# SCH_Aether_Zero_R0_3.net
KiCad netlist of a schematic drawn in EasyEDA
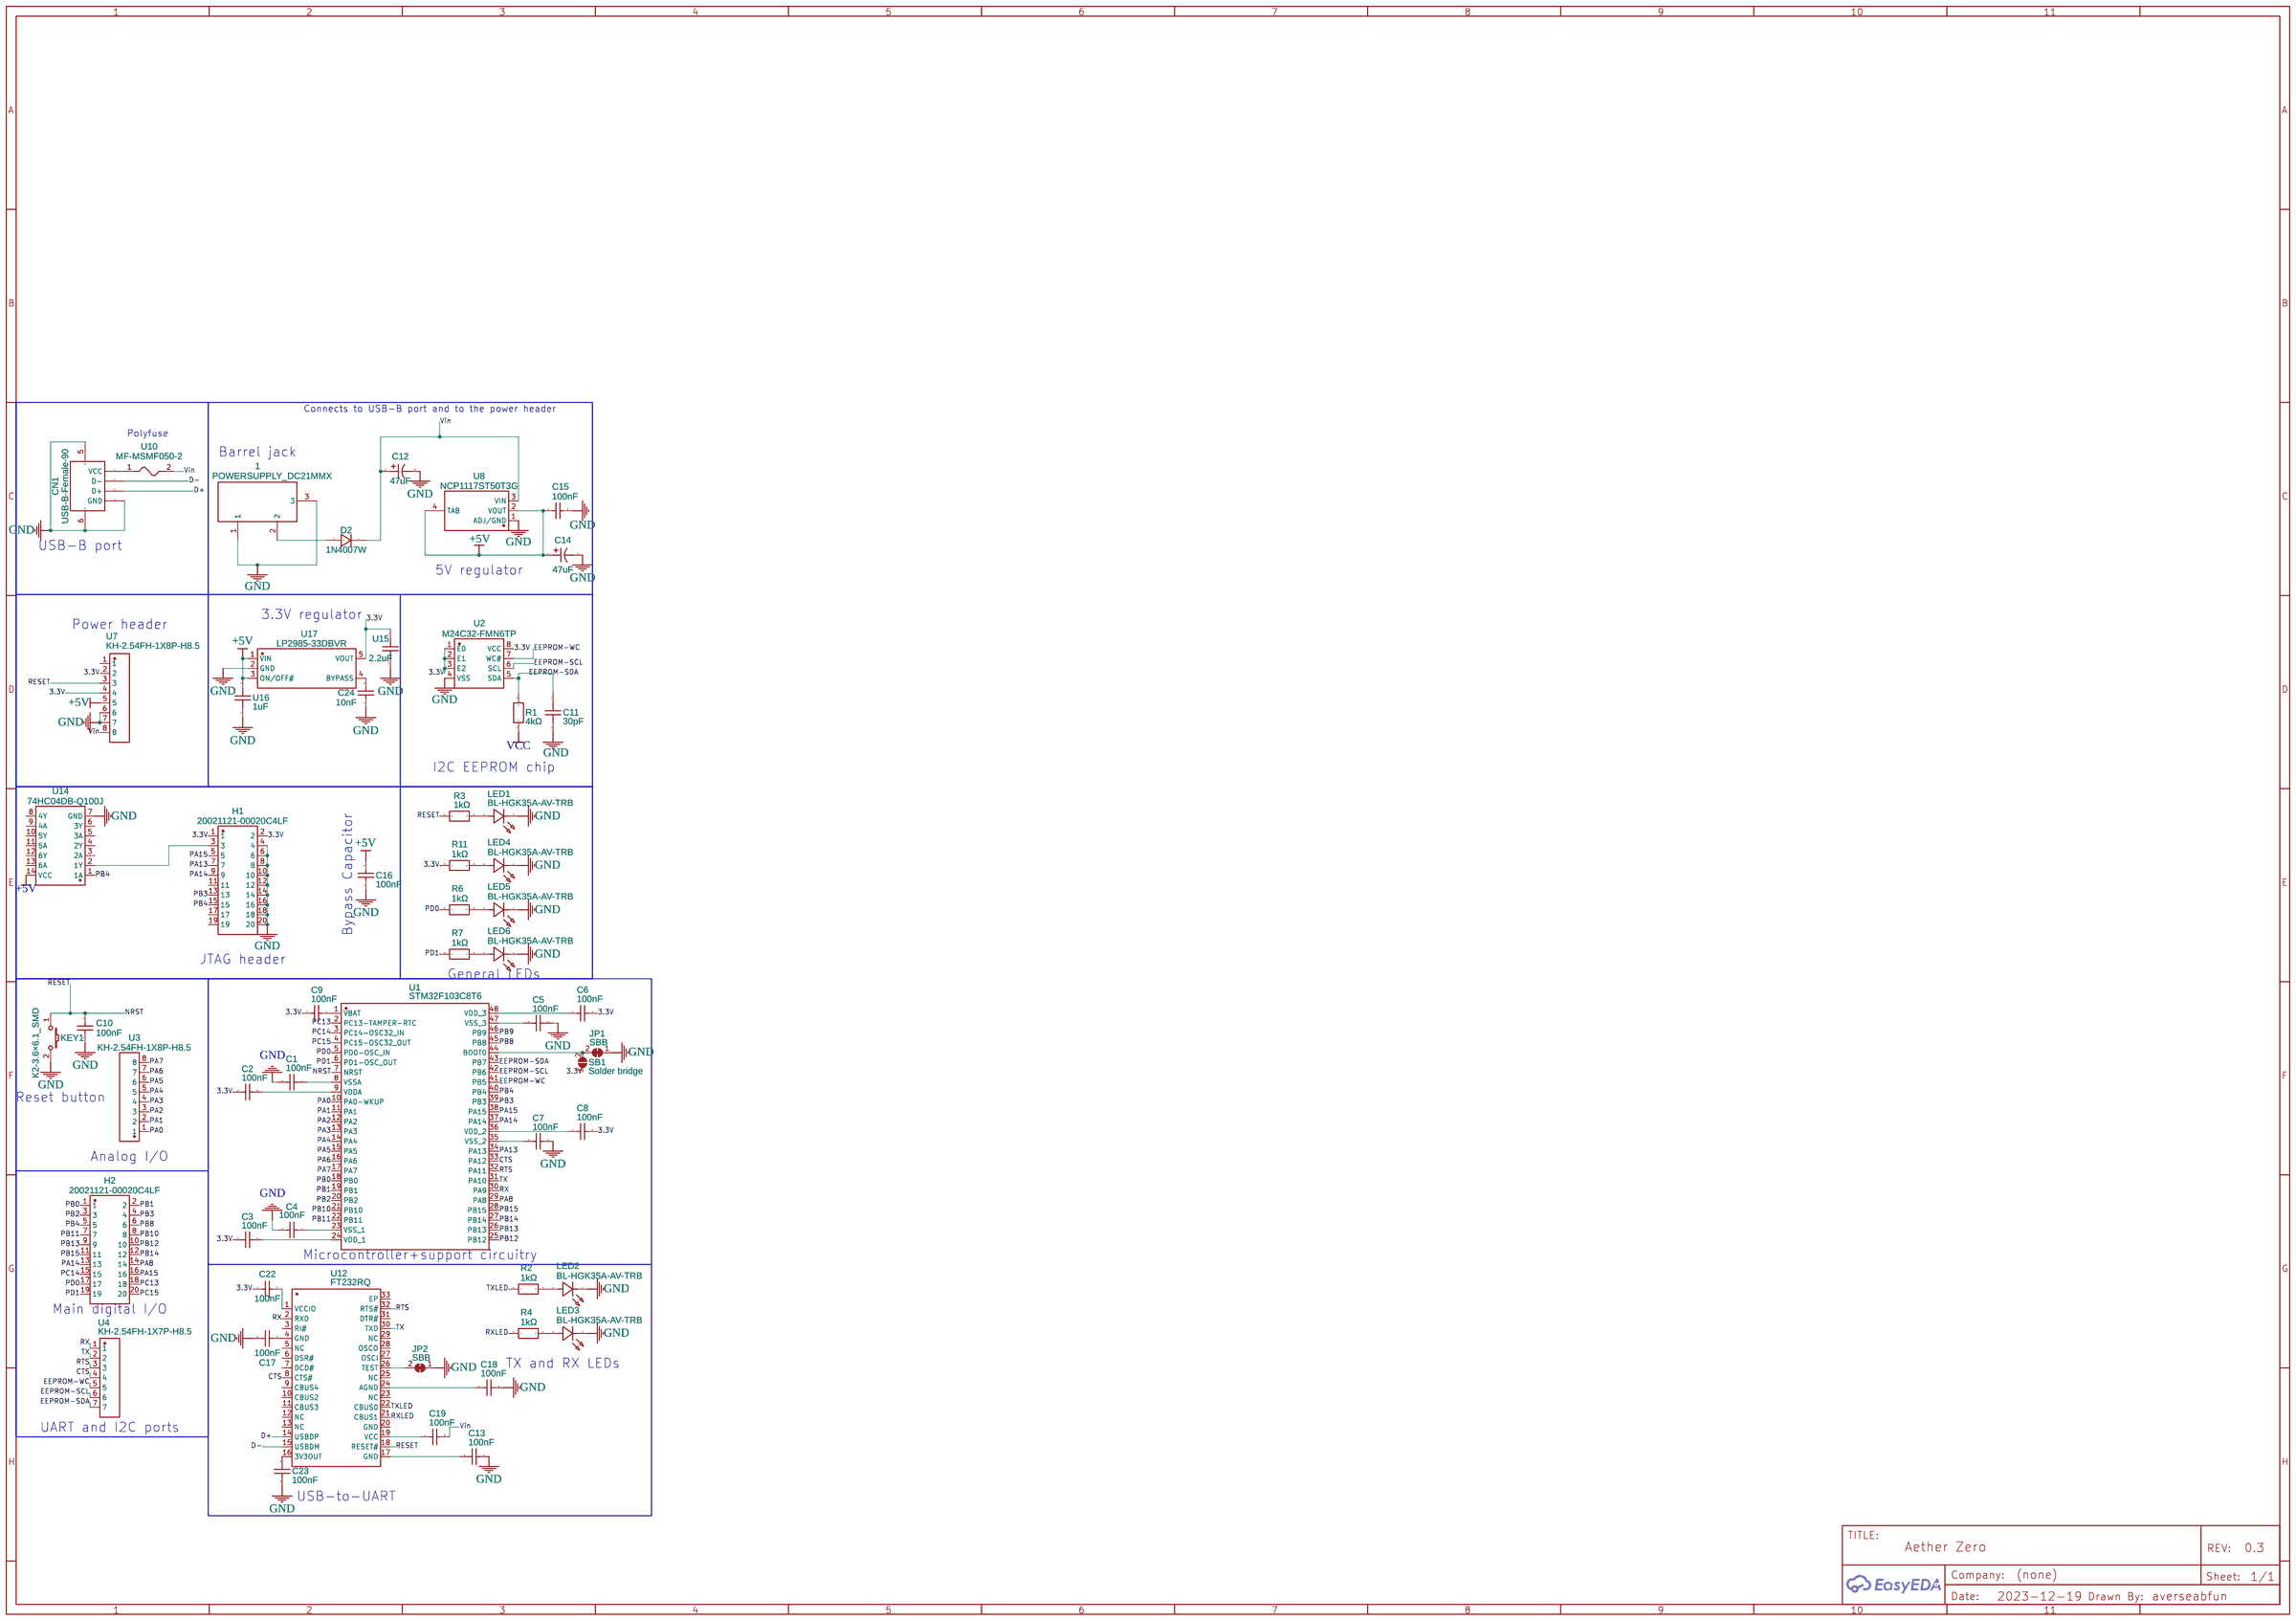
[diagram p0: schematic sheet]

(export (version "E")
  (design (tool "Eeschema 10.0.6"))
  (components
    (comp (ref "1") (value "POWERSUPPLY_DC21MMX") (libsource (lib "") (part "POWERSUPPLY_DC21MMX")))
    (comp (ref "C1")
      (value "100nF")
      (fields (field (name "Manufacturer Part") "0402B104K160NT") (field (name "Manufacturer") "FH(风华)"))
      (libsource (lib "") (part "0402B104K160NT_2"))
    )
    (comp (ref "C2")
      (value "100nF")
      (fields (field (name "Manufacturer Part") "0402B104K160NT") (field (name "Manufacturer") "FH(风华)"))
      (libsource (lib "") (part "0402B104K160NT_2"))
    )
    (comp (ref "C3")
      (value "100nF")
      (fields (field (name "Manufacturer Part") "0402B104K160NT") (field (name "Manufacturer") "FH(风华)"))
      (libsource (lib "") (part "0402B104K160NT_2"))
    )
    (comp (ref "C4")
      (value "100nF")
      (fields (field (name "Manufacturer Part") "0402B104K160NT") (field (name "Manufacturer") "FH(风华)"))
      (libsource (lib "") (part "0402B104K160NT_2"))
    )
    (comp (ref "C5")
      (value "100nF")
      (fields (field (name "Manufacturer Part") "0402B104K160NT") (field (name "Manufacturer") "FH(风华)"))
      (libsource (lib "") (part "0402B104K160NT_1"))
    )
    (comp (ref "C6")
      (value "100nF")
      (fields (field (name "Manufacturer Part") "0402B104K160NT") (field (name "Manufacturer") "FH(风华)"))
      (libsource (lib "") (part "0402B104K160NT_1"))
    )
    (comp (ref "C7")
      (value "100nF")
      (fields (field (name "Manufacturer Part") "0402B104K160NT") (field (name "Manufacturer") "FH(风华)"))
      (libsource (lib "") (part "0402B104K160NT_1"))
    )
    (comp (ref "C8")
      (value "100nF")
      (fields (field (name "Manufacturer Part") "0402B104K160NT") (field (name "Manufacturer") "FH(风华)"))
      (libsource (lib "") (part "0402B104K160NT_1"))
    )
    (comp (ref "C9")
      (value "100nF")
      (fields (field (name "Manufacturer Part") "0402B104K160NT") (field (name "Manufacturer") "FH(风华)"))
      (libsource (lib "") (part "0402B104K160NT_2"))
    )
    (comp (ref "C10")
      (value "100nF")
      (fields (field (name "Manufacturer Part") "0402B104K160NT") (field (name "Manufacturer") "FH(风华)"))
      (libsource (lib "") (part "0402B104K160NT"))
    )
    (comp (ref "C11")
      (value "30pF")
      (fields
        (field (name "Manufacturer Part") "AC0402JRNPO9BN300")
        (field (name "Manufacturer") "YAGEO(国巨)")
      )
      (libsource (lib "") (part "AC0402JRNPO9BN300"))
    )
    (comp (ref "C12")
      (value "47uF")
      (fields
        (field (name "Manufacturer Part") "RVT47UF35V67RV0039")
        (field (name "Manufacturer") "KNSCHA(科尼盛)")
      )
      (libsource (lib "") (part "RVT47UF35V67RV0039"))
    )
    (comp (ref "C13")
      (value "100nF")
      (fields (field (name "Manufacturer Part") "0402B104K160NT") (field (name "Manufacturer") "FH(风华)"))
      (libsource (lib "") (part "0402B104K160NT_1"))
    )
    (comp (ref "C14")
      (value "47uF")
      (fields
        (field (name "Manufacturer Part") "RVT47UF35V67RV0039")
        (field (name "Manufacturer") "KNSCHA(科尼盛)")
      )
      (libsource (lib "") (part "RVT47UF35V67RV0039"))
    )
    (comp (ref "C15")
      (value "100nF")
      (fields (field (name "Manufacturer Part") "0402B104K160NT") (field (name "Manufacturer") "FH(风华)"))
      (libsource (lib "") (part "0402B104K160NT_1"))
    )
    (comp (ref "C16")
      (value "100nF")
      (fields (field (name "Manufacturer Part") "0402B104K160NT") (field (name "Manufacturer") "FH(风华)"))
      (libsource (lib "") (part "0402B104K160NT_3"))
    )
    (comp (ref "C17")
      (value "100nF")
      (fields (field (name "Manufacturer Part") "0402B104K160NT") (field (name "Manufacturer") "FH(风华)"))
      (libsource (lib "") (part "0402B104K160NT_2"))
    )
    (comp (ref "C18")
      (value "100nF")
      (fields (field (name "Manufacturer Part") "0402B104K160NT") (field (name "Manufacturer") "FH(风华)"))
      (libsource (lib "") (part "0402B104K160NT_1"))
    )
    (comp (ref "C19")
      (value "100nF")
      (fields (field (name "Manufacturer Part") "0402B104K160NT") (field (name "Manufacturer") "FH(风华)"))
      (libsource (lib "") (part "0402B104K160NT_1"))
    )
    (comp (ref "C22")
      (value "100nF")
      (fields (field (name "Manufacturer Part") "0402B104K160NT") (field (name "Manufacturer") "FH(风华)"))
      (libsource (lib "") (part "0402B104K160NT_2"))
    )
    (comp (ref "C23")
      (value "100nF")
      (fields (field (name "Manufacturer Part") "0402B104K160NT") (field (name "Manufacturer") "FH(风华)"))
      (libsource (lib "") (part "0402B104K160NT"))
    )
    (comp (ref "C24")
      (value "10nF")
      (fields (field (name "Manufacturer Part") "0402B103K500NT") (field (name "Manufacturer") "FH(风华)"))
      (libsource (lib "") (part "0402B103K500NT"))
    )
    (comp (ref "CN1")
      (value "USB-B-Female-90")
      (fields (field (name "Manufacturer Part") "921-111A1010D10200") (field (name "Manufacturer") "精拓金"))
      (libsource (lib "") (part "USB-B-Female-90"))
    )
    (comp (ref "D2")
      (value "1N4007W")
      (fields (field (name "Manufacturer") "BLUE ROCKET"))
      (libsource (lib "") (part "1N4007W"))
    )
    (comp (ref "H1")
      (value "20021121-00020C4LF")
      (fields (field (name "Manufacturer") "Amphenol"))
      (libsource (lib "") (part "20021121-00020C4LF"))
    )
    (comp (ref "H2")
      (value "20021121-00020C4LF")
      (fields (field (name "Manufacturer") "Amphenol"))
      (libsource (lib "") (part "20021121-00020C4LF"))
    )
    (comp (ref "JP1") (value "SBB") (libsource (lib "") (part "SBB")))
    (comp (ref "JP2") (value "SBB") (libsource (lib "") (part "SBB")))
    (comp (ref "KEY1")
      (value "K2-3.6×6.1_SMD")
      (fields (field (name "Manufacturer Part") "K2-1107ST-A4SW-06"))
      (libsource (lib "") (part "K2-3.6×6.1_SMD"))
    )
    (comp (ref "LED1")
      (value "BL-HGK35A-AV-TRB")
      (fields (field (name "Manufacturer") "BrtLed(佰鸿)"))
      (libsource (lib "") (part "BL-HGK35A-AV-TRB"))
    )
    (comp (ref "LED2")
      (value "BL-HGK35A-AV-TRB")
      (fields (field (name "Manufacturer") "BrtLed(佰鸿)"))
      (libsource (lib "") (part "BL-HGK35A-AV-TRB"))
    )
    (comp (ref "LED3")
      (value "BL-HGK35A-AV-TRB")
      (fields (field (name "Manufacturer") "BrtLed(佰鸿)"))
      (libsource (lib "") (part "BL-HGK35A-AV-TRB"))
    )
    (comp (ref "LED4")
      (value "BL-HGK35A-AV-TRB")
      (fields (field (name "Manufacturer") "BrtLed(佰鸿)"))
      (libsource (lib "") (part "BL-HGK35A-AV-TRB"))
    )
    (comp (ref "LED5")
      (value "BL-HGK35A-AV-TRB")
      (fields (field (name "Manufacturer") "BrtLed(佰鸿)"))
      (libsource (lib "") (part "BL-HGK35A-AV-TRB"))
    )
    (comp (ref "LED6")
      (value "BL-HGK35A-AV-TRB")
      (fields (field (name "Manufacturer") "BrtLed(佰鸿)"))
      (libsource (lib "") (part "BL-HGK35A-AV-TRB"))
    )
    (comp (ref "R1")
      (value "4kΩ")
      (fields (field (name "Manufacturer Part") "RN732BTTD4001B25") (field (name "Manufacturer") "KOA"))
      (libsource (lib "") (part "RN732BTTD4001B25"))
    )
    (comp (ref "R2")
      (value "1kΩ")
      (fields (field (name "Manufacturer Part") "CR-03JA7----1K") (field (name "Manufacturer") "Viking Tech"))
      (libsource (lib "") (part "CR-03JA7----1K"))
    )
    (comp (ref "R3")
      (value "1kΩ")
      (fields (field (name "Manufacturer Part") "CR-03JA7----1K") (field (name "Manufacturer") "Viking Tech"))
      (libsource (lib "") (part "CR-03JA7----1K_1"))
    )
    (comp (ref "R4")
      (value "1kΩ")
      (fields (field (name "Manufacturer Part") "CR-03JA7----1K") (field (name "Manufacturer") "Viking Tech"))
      (libsource (lib "") (part "CR-03JA7----1K"))
    )
    (comp (ref "R6")
      (value "1kΩ")
      (fields (field (name "Manufacturer Part") "CR-03JA7----1K") (field (name "Manufacturer") "Viking Tech"))
      (libsource (lib "") (part "CR-03JA7----1K"))
    )
    (comp (ref "R7")
      (value "1kΩ")
      (fields (field (name "Manufacturer Part") "CR-03JA7----1K") (field (name "Manufacturer") "Viking Tech"))
      (libsource (lib "") (part "CR-03JA7----1K"))
    )
    (comp (ref "R11")
      (value "1kΩ")
      (fields (field (name "Manufacturer Part") "CR-03JA7----1K") (field (name "Manufacturer") "Viking Tech"))
      (libsource (lib "") (part "CR-03JA7----1K"))
    )
    (comp (ref "SB1")
      (value "Solder bridge")
      (fields (field (name "Manufacturer Part") "DNP"))
      (libsource (lib "") (part "Solder bridge"))
    )
    (comp (ref "U1")
      (value "STM32F103C8T6")
      (fields (field (name "Manufacturer") "ST(意法半导体)"))
      (libsource (lib "") (part "STM32F103C8T6"))
    )
    (comp (ref "U2")
      (value "M24C32-FMN6TP")
      (fields (field (name "Manufacturer") "ST(意法半导体)"))
      (libsource (lib "") (part "M24C32-FMN6TP"))
    )
    (comp (ref "U3")
      (value "KH-2.54FH-1X8P-H8.5")
      (fields (field (name "Manufacturer") "kinghelm(金航标)"))
      (libsource (lib "") (part "KH-2.54FH-1X8P-H8.5_1"))
    )
    (comp (ref "U4")
      (value "KH-2.54FH-1X7P-H8.5")
      (fields (field (name "Manufacturer") "kinghelm(金航标)"))
      (libsource (lib "") (part "KH-2.54FH-1X7P-H8.5"))
    )
    (comp (ref "U7")
      (value "KH-2.54FH-1X8P-H8.5")
      (fields (field (name "Manufacturer") "kinghelm(金航标)"))
      (libsource (lib "") (part "KH-2.54FH-1X8P-H8.5"))
    )
    (comp (ref "U8")
      (value "NCP1117ST50T3G")
      (fields (field (name "Manufacturer") "onsemi(安森美)"))
      (libsource (lib "") (part "NCP1117ST50T3G"))
    )
    (comp (ref "U10")
      (value "MF-MSMF050-2")
      (fields (field (name "Manufacturer") "BOURNS"))
      (libsource (lib "") (part "MF-MSMF050-2"))
    )
    (comp (ref "U12")
      (value "FT232RQ")
      (fields (field (name "Manufacturer Part") "FT232RQ-REEL") (field (name "Manufacturer") "FTDI(飞特帝亚)"))
      (libsource (lib "") (part "FT232RQ"))
    )
    (comp (ref "U14")
      (value "74HC04DB-Q100J")
      (fields (field (name "Manufacturer") "Nexperia(安世)"))
      (libsource (lib "") (part "74HC04DB-Q100J"))
    )
    (comp (ref "U15")
      (value "2.2uF")
      (fields (field (name "Manufacturer Part") "0805X225K250CT") (field (name "Manufacturer") "Walsin(华新科)"))
      (libsource (lib "") (part "0805X225K250CT_C5122273"))
    )
    (comp (ref "U16")
      (value "1uF")
      (fields (field (name "Manufacturer Part") "CGA5L3X8R1H105KT0Y0N") (field (name "Manufacturer") "TDK"))
      (libsource (lib "") (part "CGA5L3X8R1H105KT0Y0N"))
    )
    (comp (ref "U17")
      (value "LP2985-33DBVR")
      (fields (field (name "Manufacturer") "TI(德州仪器)"))
      (libsource (lib "") (part "LP2985-33DBVR"))
    )
  )
  (nets
    (net (code "1") (name "+5V") (class "Default")
      (node (ref "C14") (pin "1") (pinfunction "1_1") (pintype "input"))
      (node (ref "C15") (pin "1") (pinfunction "1_1") (pintype "input"))
      (node (ref "C16") (pin "2") (pinfunction "2_2") (pintype "input"))
      (node (ref "U14") (pin "14") (pinfunction "VCC_14") (pintype "unspecified"))
      (node (ref "U16") (pin "2") (pinfunction "2_2") (pintype "unspecified"))
      (node (ref "U17") (pin "1") (pinfunction "VIN_1") (pintype "unspecified"))
      (node (ref "U17") (pin "3") (pinfunction "ON/OFF#_3") (pintype "unspecified"))
      (node (ref "U7") (pin "5") (pinfunction "5_5") (pintype "unspecified"))
      (node (ref "U8") (pin "2") (pinfunction "VOUT_2") (pintype "unspecified"))
      (node (ref "U8") (pin "4") (pinfunction "TAB_4") (pintype "unspecified"))
    )
    (net (code "2") (name "/3.3V") (class "Default")
      (node (ref "C2") (pin "2") (pinfunction "2_2") (pintype "input"))
      (node (ref "C22") (pin "2") (pinfunction "2_2") (pintype "input"))
      (node (ref "C3") (pin "2") (pinfunction "2_2") (pintype "input"))
      (node (ref "C6") (pin "2") (pinfunction "2_2") (pintype "input"))
      (node (ref "C8") (pin "2") (pinfunction "2_2") (pintype "input"))
      (node (ref "C9") (pin "2") (pinfunction "2_2") (pintype "input"))
      (node (ref "H1") (pin "1") (pinfunction "1_1") (pintype "unspecified"))
      (node (ref "H1") (pin "2") (pinfunction "2_2") (pintype "unspecified"))
      (node (ref "R11") (pin "1") (pinfunction "1_1") (pintype "unspecified"))
      (node (ref "SB1") (pin "1") (pinfunction "A_1") (pintype "unspecified"))
      (node (ref "U15") (pin "1") (pinfunction "1_1") (pintype "unspecified"))
      (node (ref "U17") (pin "5") (pinfunction "VOUT_5") (pintype "unspecified"))
      (node (ref "U2") (pin "1") (pinfunction "E0_1") (pintype "unspecified"))
      (node (ref "U2") (pin "2") (pinfunction "E1_2") (pintype "unspecified"))
      (node (ref "U2") (pin "3") (pinfunction "E2_3") (pintype "unspecified"))
      (node (ref "U2") (pin "8") (pinfunction "VCC_8") (pintype "unspecified"))
      (node (ref "U7") (pin "2") (pinfunction "2_2") (pintype "unspecified"))
      (node (ref "U7") (pin "4") (pinfunction "4_4") (pintype "unspecified"))
    )
    (net (code "3") (name "/CTS") (class "Default")
      (node (ref "U1") (pin "33") (pinfunction "PA12_33") (pintype "unspecified"))
      (node (ref "U12") (pin "8") (pinfunction "CTS#_8") (pintype "unspecified"))
      (node (ref "U4") (pin "4") (pinfunction "4_4") (pintype "unspecified"))
    )
    (net (code "4") (name "/D+") (class "Default")
      (node (ref "CN1") (pin "3") (pinfunction "D+_3") (pintype "input"))
      (node (ref "U12") (pin "14") (pinfunction "USBDP_14") (pintype "unspecified"))
    )
    (net (code "5") (name "/D-") (class "Default")
      (node (ref "CN1") (pin "2") (pinfunction "D-_2") (pintype "input"))
      (node (ref "U12") (pin "15") (pinfunction "USBDM_15") (pintype "unspecified"))
    )
    (net (code "6") (name "/EEPROM-SCL") (class "Default")
      (node (ref "U1") (pin "42") (pinfunction "PB6_42") (pintype "unspecified"))
      (node (ref "U2") (pin "6") (pinfunction "SCL_6") (pintype "unspecified"))
      (node (ref "U4") (pin "6") (pinfunction "6_6") (pintype "unspecified"))
    )
    (net (code "7") (name "/EEPROM-SDA") (class "Default")
      (node (ref "C11") (pin "1") (pinfunction "1_1") (pintype "unspecified"))
      (node (ref "R1") (pin "2") (pinfunction "2_2") (pintype "unspecified"))
      (node (ref "U1") (pin "43") (pinfunction "PB7_43") (pintype "unspecified"))
      (node (ref "U2") (pin "5") (pinfunction "SDA_5") (pintype "unspecified"))
      (node (ref "U4") (pin "7") (pinfunction "7_7") (pintype "unspecified"))
    )
    (net (code "8") (name "/EEPROM-WC") (class "Default")
      (node (ref "U1") (pin "41") (pinfunction "PB5_41") (pintype "unspecified"))
      (node (ref "U2") (pin "7") (pinfunction "WC#_7") (pintype "unspecified"))
      (node (ref "U4") (pin "5") (pinfunction "5_5") (pintype "unspecified"))
    )
    (net (code "9") (name "/NRST") (class "Default")
      (node (ref "C10") (pin "1") (pinfunction "1_1") (pintype "input"))
      (node (ref "KEY1") (pin "1") (pinfunction "1_1") (pintype "unspecified"))
      (node (ref "R3") (pin "2") (pinfunction "2_2") (pintype "unspecified"))
      (node (ref "U1") (pin "7") (pinfunction "NRST_7") (pintype "unspecified"))
      (node (ref "U12") (pin "18") (pinfunction "RESET#_18") (pintype "unspecified"))
      (node (ref "U7") (pin "3") (pinfunction "3_3") (pintype "unspecified"))
    )
    (net (code "10") (name "/PA0") (class "Default")
      (node (ref "U1") (pin "10") (pinfunction "PA0-WKUP_10") (pintype "unspecified"))
      (node (ref "U3") (pin "1") (pinfunction "1_1") (pintype "unspecified"))
    )
    (net (code "11") (name "/PA1") (class "Default")
      (node (ref "U1") (pin "11") (pinfunction "PA1_11") (pintype "unspecified"))
      (node (ref "U3") (pin "2") (pinfunction "2_2") (pintype "unspecified"))
    )
    (net (code "12") (name "/PA2") (class "Default")
      (node (ref "U1") (pin "12") (pinfunction "PA2_12") (pintype "unspecified"))
      (node (ref "U3") (pin "3") (pinfunction "3_3") (pintype "unspecified"))
    )
    (net (code "13") (name "/PA3") (class "Default")
      (node (ref "U1") (pin "13") (pinfunction "PA3_13") (pintype "unspecified"))
      (node (ref "U3") (pin "4") (pinfunction "4_4") (pintype "unspecified"))
    )
    (net (code "14") (name "/PA4") (class "Default")
      (node (ref "U1") (pin "14") (pinfunction "PA4_14") (pintype "unspecified"))
      (node (ref "U3") (pin "5") (pinfunction "5_5") (pintype "unspecified"))
    )
    (net (code "15") (name "/PA5") (class "Default")
      (node (ref "U1") (pin "15") (pinfunction "PA5_15") (pintype "unspecified"))
      (node (ref "U3") (pin "6") (pinfunction "6_6") (pintype "unspecified"))
    )
    (net (code "16") (name "/PA6") (class "Default")
      (node (ref "U1") (pin "16") (pinfunction "PA6_16") (pintype "unspecified"))
      (node (ref "U3") (pin "7") (pinfunction "7_7") (pintype "unspecified"))
    )
    (net (code "17") (name "/PA7") (class "Default")
      (node (ref "U1") (pin "17") (pinfunction "PA7_17") (pintype "unspecified"))
      (node (ref "U3") (pin "8") (pinfunction "8_8") (pintype "unspecified"))
    )
    (net (code "18") (name "/PA8") (class "Default")
      (node (ref "H2") (pin "14") (pinfunction "14_14") (pintype "unspecified"))
      (node (ref "U1") (pin "29") (pinfunction "PA8_29") (pintype "unspecified"))
    )
    (net (code "19") (name "/PA13") (class "Default")
      (node (ref "H1") (pin "7") (pinfunction "7_7") (pintype "unspecified"))
      (node (ref "U1") (pin "34") (pinfunction "PA13_34") (pintype "unspecified"))
    )
    (net (code "20") (name "/PA14") (class "Default")
      (node (ref "H1") (pin "9") (pinfunction "9_9") (pintype "unspecified"))
      (node (ref "H2") (pin "13") (pinfunction "13_13") (pintype "unspecified"))
      (node (ref "U1") (pin "37") (pinfunction "PA14_37") (pintype "unspecified"))
    )
    (net (code "21") (name "/PA15") (class "Default")
      (node (ref "H1") (pin "5") (pinfunction "5_5") (pintype "unspecified"))
      (node (ref "H2") (pin "16") (pinfunction "16_16") (pintype "unspecified"))
      (node (ref "U1") (pin "38") (pinfunction "PA15_38") (pintype "unspecified"))
    )
    (net (code "22") (name "/PB0") (class "Default")
      (node (ref "H2") (pin "1") (pinfunction "1_1") (pintype "unspecified"))
      (node (ref "U1") (pin "18") (pinfunction "PB0_18") (pintype "unspecified"))
    )
    (net (code "23") (name "/PB1") (class "Default")
      (node (ref "H2") (pin "2") (pinfunction "2_2") (pintype "unspecified"))
      (node (ref "U1") (pin "19") (pinfunction "PB1_19") (pintype "unspecified"))
    )
    (net (code "24") (name "/PB2") (class "Default")
      (node (ref "H2") (pin "3") (pinfunction "3_3") (pintype "unspecified"))
      (node (ref "U1") (pin "20") (pinfunction "PB2_20") (pintype "unspecified"))
    )
    (net (code "25") (name "/PB3") (class "Default")
      (node (ref "H1") (pin "13") (pinfunction "13_13") (pintype "unspecified"))
      (node (ref "H2") (pin "4") (pinfunction "4_4") (pintype "unspecified"))
      (node (ref "U1") (pin "39") (pinfunction "PB3_39") (pintype "unspecified"))
    )
    (net (code "26") (name "/PB4") (class "Default")
      (node (ref "H1") (pin "15") (pinfunction "15_15") (pintype "unspecified"))
      (node (ref "H2") (pin "5") (pinfunction "5_5") (pintype "unspecified"))
      (node (ref "U1") (pin "40") (pinfunction "PB4_40") (pintype "unspecified"))
      (node (ref "U14") (pin "1") (pinfunction "1A_1") (pintype "unspecified"))
    )
    (net (code "27") (name "/PB8") (class "Default")
      (node (ref "H2") (pin "6") (pinfunction "6_6") (pintype "unspecified"))
      (node (ref "U1") (pin "45") (pinfunction "PB8_45") (pintype "unspecified"))
    )
    (net (code "28") (name "/PB9") (class "Default")
      (node (ref "U1") (pin "46") (pinfunction "PB9_46") (pintype "unspecified"))
    )
    (net (code "29") (name "/PB10") (class "Default")
      (node (ref "H2") (pin "8") (pinfunction "8_8") (pintype "unspecified"))
      (node (ref "U1") (pin "21") (pinfunction "PB10_21") (pintype "unspecified"))
    )
    (net (code "30") (name "/PB11") (class "Default")
      (node (ref "H2") (pin "7") (pinfunction "7_7") (pintype "unspecified"))
      (node (ref "U1") (pin "22") (pinfunction "PB11_22") (pintype "unspecified"))
    )
    (net (code "31") (name "/PB12") (class "Default")
      (node (ref "H2") (pin "10") (pinfunction "10_10") (pintype "unspecified"))
      (node (ref "U1") (pin "25") (pinfunction "PB12_25") (pintype "unspecified"))
    )
    (net (code "32") (name "/PB13") (class "Default")
      (node (ref "H2") (pin "9") (pinfunction "9_9") (pintype "unspecified"))
      (node (ref "U1") (pin "26") (pinfunction "PB13_26") (pintype "unspecified"))
    )
    (net (code "33") (name "/PB14") (class "Default")
      (node (ref "H2") (pin "12") (pinfunction "12_12") (pintype "unspecified"))
      (node (ref "U1") (pin "27") (pinfunction "PB14_27") (pintype "unspecified"))
    )
    (net (code "34") (name "/PB15") (class "Default")
      (node (ref "H2") (pin "11") (pinfunction "11_11") (pintype "unspecified"))
      (node (ref "U1") (pin "28") (pinfunction "PB15_28") (pintype "unspecified"))
    )
    (net (code "35") (name "/PC13") (class "Default")
      (node (ref "H2") (pin "18") (pinfunction "18_18") (pintype "unspecified"))
      (node (ref "U1") (pin "2") (pinfunction "PC13-TAMPER-RTC_2") (pintype "unspecified"))
    )
    (net (code "36") (name "/PC14") (class "Default")
      (node (ref "H2") (pin "15") (pinfunction "15_15") (pintype "unspecified"))
      (node (ref "U1") (pin "3") (pinfunction "PC14-OSC32_IN_3") (pintype "unspecified"))
    )
    (net (code "37") (name "/PC15") (class "Default")
      (node (ref "H2") (pin "20") (pinfunction "20_20") (pintype "unspecified"))
      (node (ref "U1") (pin "4") (pinfunction "PC15-OSC32_OUT_4") (pintype "unspecified"))
    )
    (net (code "38") (name "/PD0") (class "Default")
      (node (ref "H2") (pin "17") (pinfunction "17_17") (pintype "unspecified"))
      (node (ref "R6") (pin "1") (pinfunction "1_1") (pintype "unspecified"))
      (node (ref "U1") (pin "5") (pinfunction "PD0-OSC_IN_5") (pintype "unspecified"))
    )
    (net (code "39") (name "/PD1") (class "Default")
      (node (ref "H2") (pin "19") (pinfunction "19_19") (pintype "unspecified"))
      (node (ref "R7") (pin "1") (pinfunction "1_1") (pintype "unspecified"))
      (node (ref "U1") (pin "6") (pinfunction "PD1-OSC_OUT_6") (pintype "unspecified"))
    )
    (net (code "40") (name "/RTS") (class "Default")
      (node (ref "U1") (pin "32") (pinfunction "PA11_32") (pintype "unspecified"))
      (node (ref "U12") (pin "32") (pinfunction "RTS#_32") (pintype "unspecified"))
      (node (ref "U4") (pin "3") (pinfunction "3_3") (pintype "unspecified"))
    )
    (net (code "41") (name "/RX") (class "Default")
      (node (ref "U1") (pin "30") (pinfunction "PA9_30") (pintype "unspecified"))
      (node (ref "U12") (pin "2") (pinfunction "RXD_2") (pintype "unspecified"))
      (node (ref "U4") (pin "1") (pinfunction "1_1") (pintype "unspecified"))
    )
    (net (code "42") (name "/RXLED") (class "Default")
      (node (ref "R4") (pin "1") (pinfunction "1_1") (pintype "unspecified"))
      (node (ref "U12") (pin "21") (pinfunction "CBUS1_21") (pintype "unspecified"))
    )
    (net (code "43") (name "/TX") (class "Default")
      (node (ref "U1") (pin "31") (pinfunction "PA10_31") (pintype "unspecified"))
      (node (ref "U12") (pin "30") (pinfunction "TXD_30") (pintype "unspecified"))
      (node (ref "U4") (pin "2") (pinfunction "2_2") (pintype "unspecified"))
    )
    (net (code "44") (name "/TXLED") (class "Default")
      (node (ref "R2") (pin "1") (pinfunction "1_1") (pintype "unspecified"))
      (node (ref "U12") (pin "22") (pinfunction "CBUS0_22") (pintype "unspecified"))
    )
    (net (code "45") (name "/Vin") (class "Default")
      (node (ref "C12") (pin "1") (pinfunction "1_1") (pintype "input"))
      (node (ref "C19") (pin "2") (pinfunction "2_2") (pintype "input"))
      (node (ref "D2") (pin "1") (pinfunction "1_1") (pintype "unspecified"))
      (node (ref "U10") (pin "2") (pinfunction "2_2") (pintype "unspecified"))
      (node (ref "U7") (pin "8") (pinfunction "8_8") (pintype "unspecified"))
      (node (ref "U8") (pin "3") (pinfunction "VIN_3") (pintype "unspecified"))
    )
    (net (code "46") (name "GND") (class "Default")
      (node (ref "1") (pin "1") (pinfunction "1_1") (pintype "bidirectional"))
      (node (ref "1") (pin "3") (pinfunction "3_3") (pintype "bidirectional"))
      (node (ref "C1") (pin "2") (pinfunction "2_2") (pintype "input"))
      (node (ref "C10") (pin "2") (pinfunction "2_2") (pintype "input"))
      (node (ref "C11") (pin "2") (pinfunction "2_2") (pintype "unspecified"))
      (node (ref "C12") (pin "2") (pinfunction "2_2") (pintype "input"))
      (node (ref "C13") (pin "2") (pinfunction "2_2") (pintype "input"))
      (node (ref "C14") (pin "2") (pinfunction "2_2") (pintype "input"))
      (node (ref "C15") (pin "2") (pinfunction "2_2") (pintype "input"))
      (node (ref "C16") (pin "1") (pinfunction "1_1") (pintype "input"))
      (node (ref "C17") (pin "2") (pinfunction "2_2") (pintype "input"))
      (node (ref "C18") (pin "2") (pinfunction "2_2") (pintype "input"))
      (node (ref "C23") (pin "2") (pinfunction "2_2") (pintype "input"))
      (node (ref "C24") (pin "1") (pinfunction "1_1") (pintype "input"))
      (node (ref "C4") (pin "2") (pinfunction "2_2") (pintype "input"))
      (node (ref "C5") (pin "2") (pinfunction "2_2") (pintype "input"))
      (node (ref "C7") (pin "2") (pinfunction "2_2") (pintype "input"))
      (node (ref "CN1") (pin "4") (pinfunction "GND_4") (pintype "input"))
      (node (ref "CN1") (pin "5") (pinfunction "SH1_5") (pintype "unspecified"))
      (node (ref "CN1") (pin "6") (pinfunction "SH2_6") (pintype "unspecified"))
      (node (ref "H1") (pin "10") (pinfunction "10_10") (pintype "unspecified"))
      (node (ref "H1") (pin "12") (pinfunction "12_12") (pintype "unspecified"))
      (node (ref "H1") (pin "14") (pinfunction "14_14") (pintype "unspecified"))
      (node (ref "H1") (pin "16") (pinfunction "16_16") (pintype "unspecified"))
      (node (ref "H1") (pin "18") (pinfunction "18_18") (pintype "unspecified"))
      (node (ref "H1") (pin "20") (pinfunction "20_20") (pintype "unspecified"))
      (node (ref "H1") (pin "4") (pinfunction "4_4") (pintype "unspecified"))
      (node (ref "H1") (pin "6") (pinfunction "6_6") (pintype "unspecified"))
      (node (ref "H1") (pin "8") (pinfunction "8_8") (pintype "unspecified"))
      (node (ref "JP1") (pin "1") (pinfunction "A_1") (pintype "unspecified"))
      (node (ref "JP2") (pin "1") (pinfunction "A_1") (pintype "unspecified"))
      (node (ref "KEY1") (pin "2") (pinfunction "2_2") (pintype "unspecified"))
      (node (ref "LED1") (pin "1") (pinfunction "K_1") (pintype "unspecified"))
      (node (ref "LED2") (pin "1") (pinfunction "K_1") (pintype "unspecified"))
      (node (ref "LED3") (pin "1") (pinfunction "K_1") (pintype "unspecified"))
      (node (ref "LED4") (pin "1") (pinfunction "K_1") (pintype "unspecified"))
      (node (ref "LED5") (pin "1") (pinfunction "K_1") (pintype "unspecified"))
      (node (ref "LED6") (pin "1") (pinfunction "K_1") (pintype "unspecified"))
      (node (ref "U14") (pin "7") (pinfunction "GND_7") (pintype "unspecified"))
      (node (ref "U15") (pin "2") (pinfunction "2_2") (pintype "unspecified"))
      (node (ref "U16") (pin "1") (pinfunction "1_1") (pintype "unspecified"))
      (node (ref "U17") (pin "2") (pinfunction "GND_2") (pintype "unspecified"))
      (node (ref "U2") (pin "4") (pinfunction "VSS_4") (pintype "unspecified"))
      (node (ref "U7") (pin "6") (pinfunction "6_6") (pintype "unspecified"))
      (node (ref "U7") (pin "7") (pinfunction "7_7") (pintype "unspecified"))
      (node (ref "U8") (pin "1") (pinfunction "ADJ/GND_1") (pintype "unspecified"))
    )
    (net (code "47") (name "Net-(1-Pad2)") (class "Default")
      (node (ref "1") (pin "2") (pinfunction "2_2") (pintype "bidirectional"))
      (node (ref "D2") (pin "2") (pinfunction "2_2") (pintype "unspecified"))
    )
    (net (code "48") (name "Net-(C13-Pad1)") (class "Default")
      (node (ref "C13") (pin "1") (pinfunction "1_1") (pintype "input"))
      (node (ref "U12") (pin "17") (pinfunction "GND_17") (pintype "unspecified"))
    )
    (net (code "49") (name "Net-(C17-Pad1)") (class "Default")
      (node (ref "C17") (pin "1") (pinfunction "1_1") (pintype "input"))
      (node (ref "U12") (pin "4") (pinfunction "GND_4") (pintype "unspecified"))
    )
    (net (code "50") (name "Net-(CN1-VCC)") (class "Default")
      (node (ref "CN1") (pin "1") (pinfunction "VCC_1") (pintype "input"))
      (node (ref "U10") (pin "1") (pinfunction "1_1") (pintype "unspecified"))
    )
    (net (code "51") (name "Net-(JP1-B)") (class "Default")
      (node (ref "JP1") (pin "2") (pinfunction "B_2") (pintype "unspecified"))
      (node (ref "SB1") (pin "2") (pinfunction "B_2") (pintype "unspecified"))
      (node (ref "U1") (pin "44") (pinfunction "BOOT0_44") (pintype "unspecified"))
    )
    (net (code "52") (name "Net-(JP2-B)") (class "Default")
      (node (ref "JP2") (pin "2") (pinfunction "B_2") (pintype "unspecified"))
      (node (ref "U12") (pin "26") (pinfunction "TEST_26") (pintype "unspecified"))
    )
    (net (code "53") (name "Net-(LED1-A)") (class "Default")
      (node (ref "LED1") (pin "2") (pinfunction "A_2") (pintype "unspecified"))
      (node (ref "R3") (pin "1") (pinfunction "1_1") (pintype "unspecified"))
    )
    (net (code "54") (name "Net-(LED2-A)") (class "Default")
      (node (ref "LED2") (pin "2") (pinfunction "A_2") (pintype "unspecified"))
      (node (ref "R2") (pin "2") (pinfunction "2_2") (pintype "unspecified"))
    )
    (net (code "55") (name "Net-(LED3-A)") (class "Default")
      (node (ref "LED3") (pin "2") (pinfunction "A_2") (pintype "unspecified"))
      (node (ref "R4") (pin "2") (pinfunction "2_2") (pintype "unspecified"))
    )
    (net (code "56") (name "Net-(LED4-A)") (class "Default")
      (node (ref "LED4") (pin "2") (pinfunction "A_2") (pintype "unspecified"))
      (node (ref "R11") (pin "2") (pinfunction "2_2") (pintype "unspecified"))
    )
    (net (code "57") (name "Net-(LED5-A)") (class "Default")
      (node (ref "LED5") (pin "2") (pinfunction "A_2") (pintype "unspecified"))
      (node (ref "R6") (pin "2") (pinfunction "2_2") (pintype "unspecified"))
    )
    (net (code "58") (name "Net-(LED6-A)") (class "Default")
      (node (ref "LED6") (pin "2") (pinfunction "A_2") (pintype "unspecified"))
      (node (ref "R7") (pin "2") (pinfunction "2_2") (pintype "unspecified"))
    )
    (net (code "59") (name "Net-(U1-VBAT)") (class "Default")
      (node (ref "C9") (pin "1") (pinfunction "1_1") (pintype "input"))
      (node (ref "U1") (pin "1") (pinfunction "VBAT_1") (pintype "unspecified"))
    )
    (net (code "60") (name "Net-(U1-VDDA)") (class "Default")
      (node (ref "C2") (pin "1") (pinfunction "1_1") (pintype "input"))
      (node (ref "U1") (pin "9") (pinfunction "VDDA_9") (pintype "unspecified"))
    )
    (net (code "61") (name "Net-(U1-VDD_1)") (class "Default")
      (node (ref "C3") (pin "1") (pinfunction "1_1") (pintype "input"))
      (node (ref "U1") (pin "24") (pinfunction "VDD_1_24") (pintype "unspecified"))
    )
    (net (code "62") (name "Net-(U1-VDD_2)") (class "Default")
      (node (ref "C8") (pin "1") (pinfunction "1_1") (pintype "input"))
      (node (ref "U1") (pin "36") (pinfunction "VDD_2_36") (pintype "unspecified"))
    )
    (net (code "63") (name "Net-(U1-VDD_3)") (class "Default")
      (node (ref "C6") (pin "1") (pinfunction "1_1") (pintype "input"))
      (node (ref "U1") (pin "48") (pinfunction "VDD_3_48") (pintype "unspecified"))
    )
    (net (code "64") (name "Net-(U1-VSSA)") (class "Default")
      (node (ref "C1") (pin "1") (pinfunction "1_1") (pintype "input"))
      (node (ref "U1") (pin "8") (pinfunction "VSSA_8") (pintype "unspecified"))
    )
    (net (code "65") (name "Net-(U1-VSS_1)") (class "Default")
      (node (ref "C4") (pin "1") (pinfunction "1_1") (pintype "input"))
      (node (ref "U1") (pin "23") (pinfunction "VSS_1_23") (pintype "unspecified"))
    )
    (net (code "66") (name "Net-(U1-VSS_2)") (class "Default")
      (node (ref "C7") (pin "1") (pinfunction "1_1") (pintype "input"))
      (node (ref "U1") (pin "35") (pinfunction "VSS_2_35") (pintype "unspecified"))
    )
    (net (code "67") (name "Net-(U1-VSS_3)") (class "Default")
      (node (ref "C5") (pin "1") (pinfunction "1_1") (pintype "input"))
      (node (ref "U1") (pin "47") (pinfunction "VSS_3_47") (pintype "unspecified"))
    )
    (net (code "68") (name "Net-(U12-3V3OUT)") (class "Default")
      (node (ref "C23") (pin "1") (pinfunction "1_1") (pintype "input"))
      (node (ref "U12") (pin "16") (pinfunction "3V3OUT_16") (pintype "unspecified"))
    )
    (net (code "69") (name "Net-(U12-AGND)") (class "Default")
      (node (ref "C18") (pin "1") (pinfunction "1_1") (pintype "input"))
      (node (ref "U12") (pin "24") (pinfunction "AGND_24") (pintype "unspecified"))
    )
    (net (code "70") (name "Net-(U12-VCC)") (class "Default")
      (node (ref "C19") (pin "1") (pinfunction "1_1") (pintype "input"))
      (node (ref "U12") (pin "19") (pinfunction "VCC_19") (pintype "unspecified"))
    )
    (net (code "71") (name "Net-(U12-VCCIO)") (class "Default")
      (node (ref "C22") (pin "1") (pinfunction "1_1") (pintype "input"))
      (node (ref "U12") (pin "1") (pinfunction "VCCIO_1") (pintype "unspecified"))
    )
    (net (code "72") (name "Net-(U14-1Y)") (class "Default")
      (node (ref "H1") (pin "3") (pinfunction "3_3") (pintype "unspecified"))
      (node (ref "U14") (pin "2") (pinfunction "1Y_2") (pintype "unspecified"))
    )
    (net (code "73") (name "Net-(U17-BYPASS)") (class "Default")
      (node (ref "C24") (pin "2") (pinfunction "2_2") (pintype "input"))
      (node (ref "U17") (pin "4") (pinfunction "BYPASS_4") (pintype "unspecified"))
    )
    (net (code "74") (name "VCC") (class "Default")
      (node (ref "R1") (pin "1") (pinfunction "1_1") (pintype "unspecified"))
    )
    (net (code "75") (name "unconnected-(H1-Pad11)") (class "Default")
      (node (ref "H1") (pin "11") (pinfunction "11_11") (pintype "unspecified"))
    )
    (net (code "76") (name "unconnected-(H1-Pad17)") (class "Default")
      (node (ref "H1") (pin "17") (pinfunction "17_17") (pintype "unspecified"))
    )
    (net (code "77") (name "unconnected-(H1-Pad19)") (class "Default")
      (node (ref "H1") (pin "19") (pinfunction "19_19") (pintype "unspecified"))
    )
    (net (code "78") (name "unconnected-(U7-Pad1)") (class "Default")
      (node (ref "U7") (pin "1") (pinfunction "1_1") (pintype "unspecified"))
    )
    (net (code "79") (name "unconnected-(U12-CBUS2-Pad10)") (class "Default")
      (node (ref "U12") (pin "10") (pinfunction "CBUS2_10") (pintype "unspecified"))
    )
    (net (code "80") (name "unconnected-(U12-CBUS3-Pad11)") (class "Default")
      (node (ref "U12") (pin "11") (pinfunction "CBUS3_11") (pintype "unspecified"))
    )
    (net (code "81") (name "unconnected-(U12-CBUS4-Pad9)") (class "Default")
      (node (ref "U12") (pin "9") (pinfunction "CBUS4_9") (pintype "unspecified"))
    )
    (net (code "82") (name "unconnected-(U12-DCD#-Pad7)") (class "Default")
      (node (ref "U12") (pin "7") (pinfunction "DCD#_7") (pintype "unspecified"))
    )
    (net (code "83") (name "unconnected-(U12-DSR#-Pad6)") (class "Default")
      (node (ref "U12") (pin "6") (pinfunction "DSR#_6") (pintype "unspecified"))
    )
    (net (code "84") (name "unconnected-(U12-DTR#-Pad31)") (class "Default")
      (node (ref "U12") (pin "31") (pinfunction "DTR#_31") (pintype "unspecified"))
    )
    (net (code "85") (name "unconnected-(U12-EP-Pad33)") (class "Default")
      (node (ref "U12") (pin "33") (pinfunction "EP_33") (pintype "unspecified"))
    )
    (net (code "86") (name "unconnected-(U12-GND-Pad20)") (class "Default")
      (node (ref "U12") (pin "20") (pinfunction "GND_20") (pintype "unspecified"))
    )
    (net (code "87") (name "unconnected-(U12-NC-Pad5)") (class "Default")
      (node (ref "U12") (pin "5") (pinfunction "NC_5") (pintype "unspecified"))
    )
    (net (code "88") (name "unconnected-(U12-NC-Pad12)") (class "Default")
      (node (ref "U12") (pin "12") (pinfunction "NC_12") (pintype "unspecified"))
    )
    (net (code "89") (name "unconnected-(U12-NC-Pad13)") (class "Default")
      (node (ref "U12") (pin "13") (pinfunction "NC_13") (pintype "unspecified"))
    )
    (net (code "90") (name "unconnected-(U12-NC-Pad23)") (class "Default")
      (node (ref "U12") (pin "23") (pinfunction "NC_23") (pintype "unspecified"))
    )
    (net (code "91") (name "unconnected-(U12-NC-Pad25)") (class "Default")
      (node (ref "U12") (pin "25") (pinfunction "NC_25") (pintype "unspecified"))
    )
    (net (code "92") (name "unconnected-(U12-NC-Pad29)") (class "Default")
      (node (ref "U12") (pin "29") (pinfunction "NC_29") (pintype "unspecified"))
    )
    (net (code "93") (name "unconnected-(U12-OSCI-Pad27)") (class "Default")
      (node (ref "U12") (pin "27") (pinfunction "OSCI_27") (pintype "unspecified"))
    )
    (net (code "94") (name "unconnected-(U12-OSCO-Pad28)") (class "Default")
      (node (ref "U12") (pin "28") (pinfunction "OSCO_28") (pintype "unspecified"))
    )
    (net (code "95") (name "unconnected-(U12-RI#-Pad3)") (class "Default")
      (node (ref "U12") (pin "3") (pinfunction "RI#_3") (pintype "unspecified"))
    )
    (net (code "96") (name "unconnected-(U14-2A-Pad3)") (class "Default")
      (node (ref "U14") (pin "3") (pinfunction "2A_3") (pintype "unspecified"))
    )
    (net (code "97") (name "unconnected-(U14-2Y-Pad4)") (class "Default")
      (node (ref "U14") (pin "4") (pinfunction "2Y_4") (pintype "unspecified"))
    )
    (net (code "98") (name "unconnected-(U14-3A-Pad5)") (class "Default")
      (node (ref "U14") (pin "5") (pinfunction "3A_5") (pintype "unspecified"))
    )
    (net (code "99") (name "unconnected-(U14-3Y-Pad6)") (class "Default")
      (node (ref "U14") (pin "6") (pinfunction "3Y_6") (pintype "unspecified"))
    )
    (net (code "100") (name "unconnected-(U14-4A-Pad9)") (class "Default")
      (node (ref "U14") (pin "9") (pinfunction "4A_9") (pintype "unspecified"))
    )
    (net (code "101") (name "unconnected-(U14-4Y-Pad8)") (class "Default")
      (node (ref "U14") (pin "8") (pinfunction "4Y_8") (pintype "unspecified"))
    )
    (net (code "102") (name "unconnected-(U14-5A-Pad11)") (class "Default")
      (node (ref "U14") (pin "11") (pinfunction "5A_11") (pintype "unspecified"))
    )
    (net (code "103") (name "unconnected-(U14-5Y-Pad10)") (class "Default")
      (node (ref "U14") (pin "10") (pinfunction "5Y_10") (pintype "unspecified"))
    )
    (net (code "104") (name "unconnected-(U14-6A-Pad13)") (class "Default")
      (node (ref "U14") (pin "13") (pinfunction "6A_13") (pintype "unspecified"))
    )
    (net (code "105") (name "unconnected-(U14-6Y-Pad12)") (class "Default")
      (node (ref "U14") (pin "12") (pinfunction "6Y_12") (pintype "unspecified"))
    )
  )
)
